# 1-Schematic_Synapse.net
KiCad netlist of a schematic drawn in EasyEDA
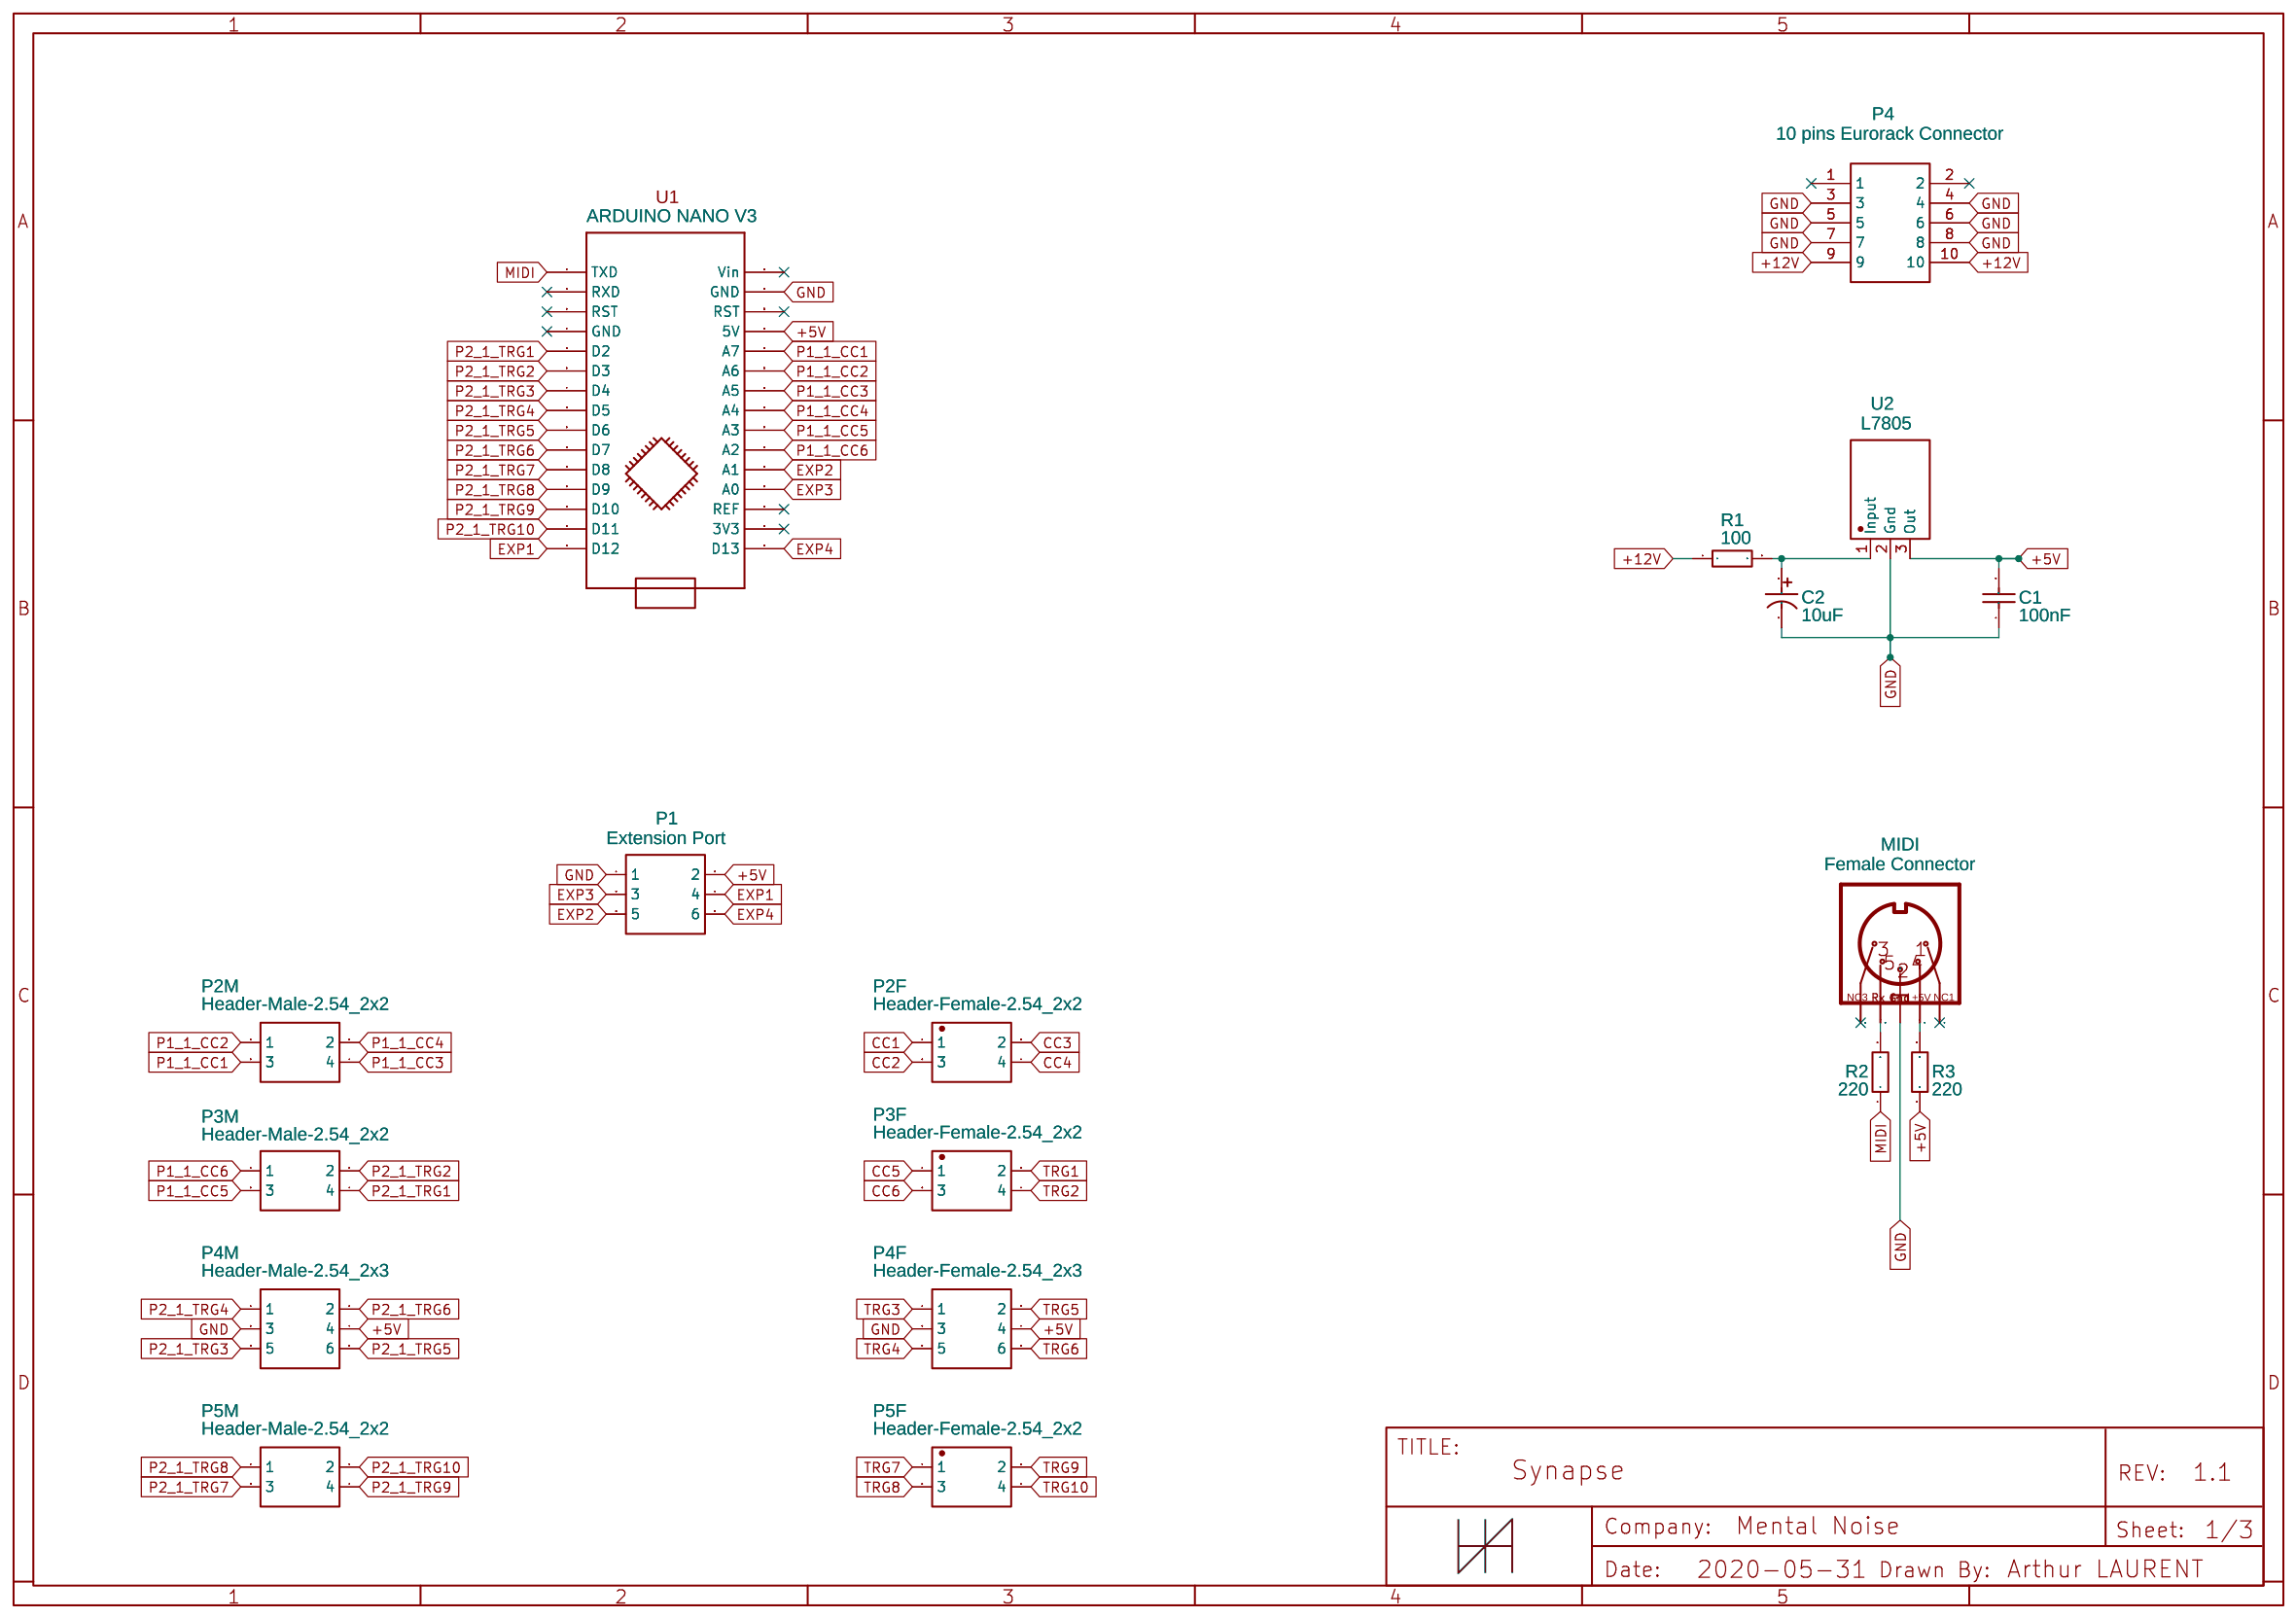
[diagram p0: Arduino]
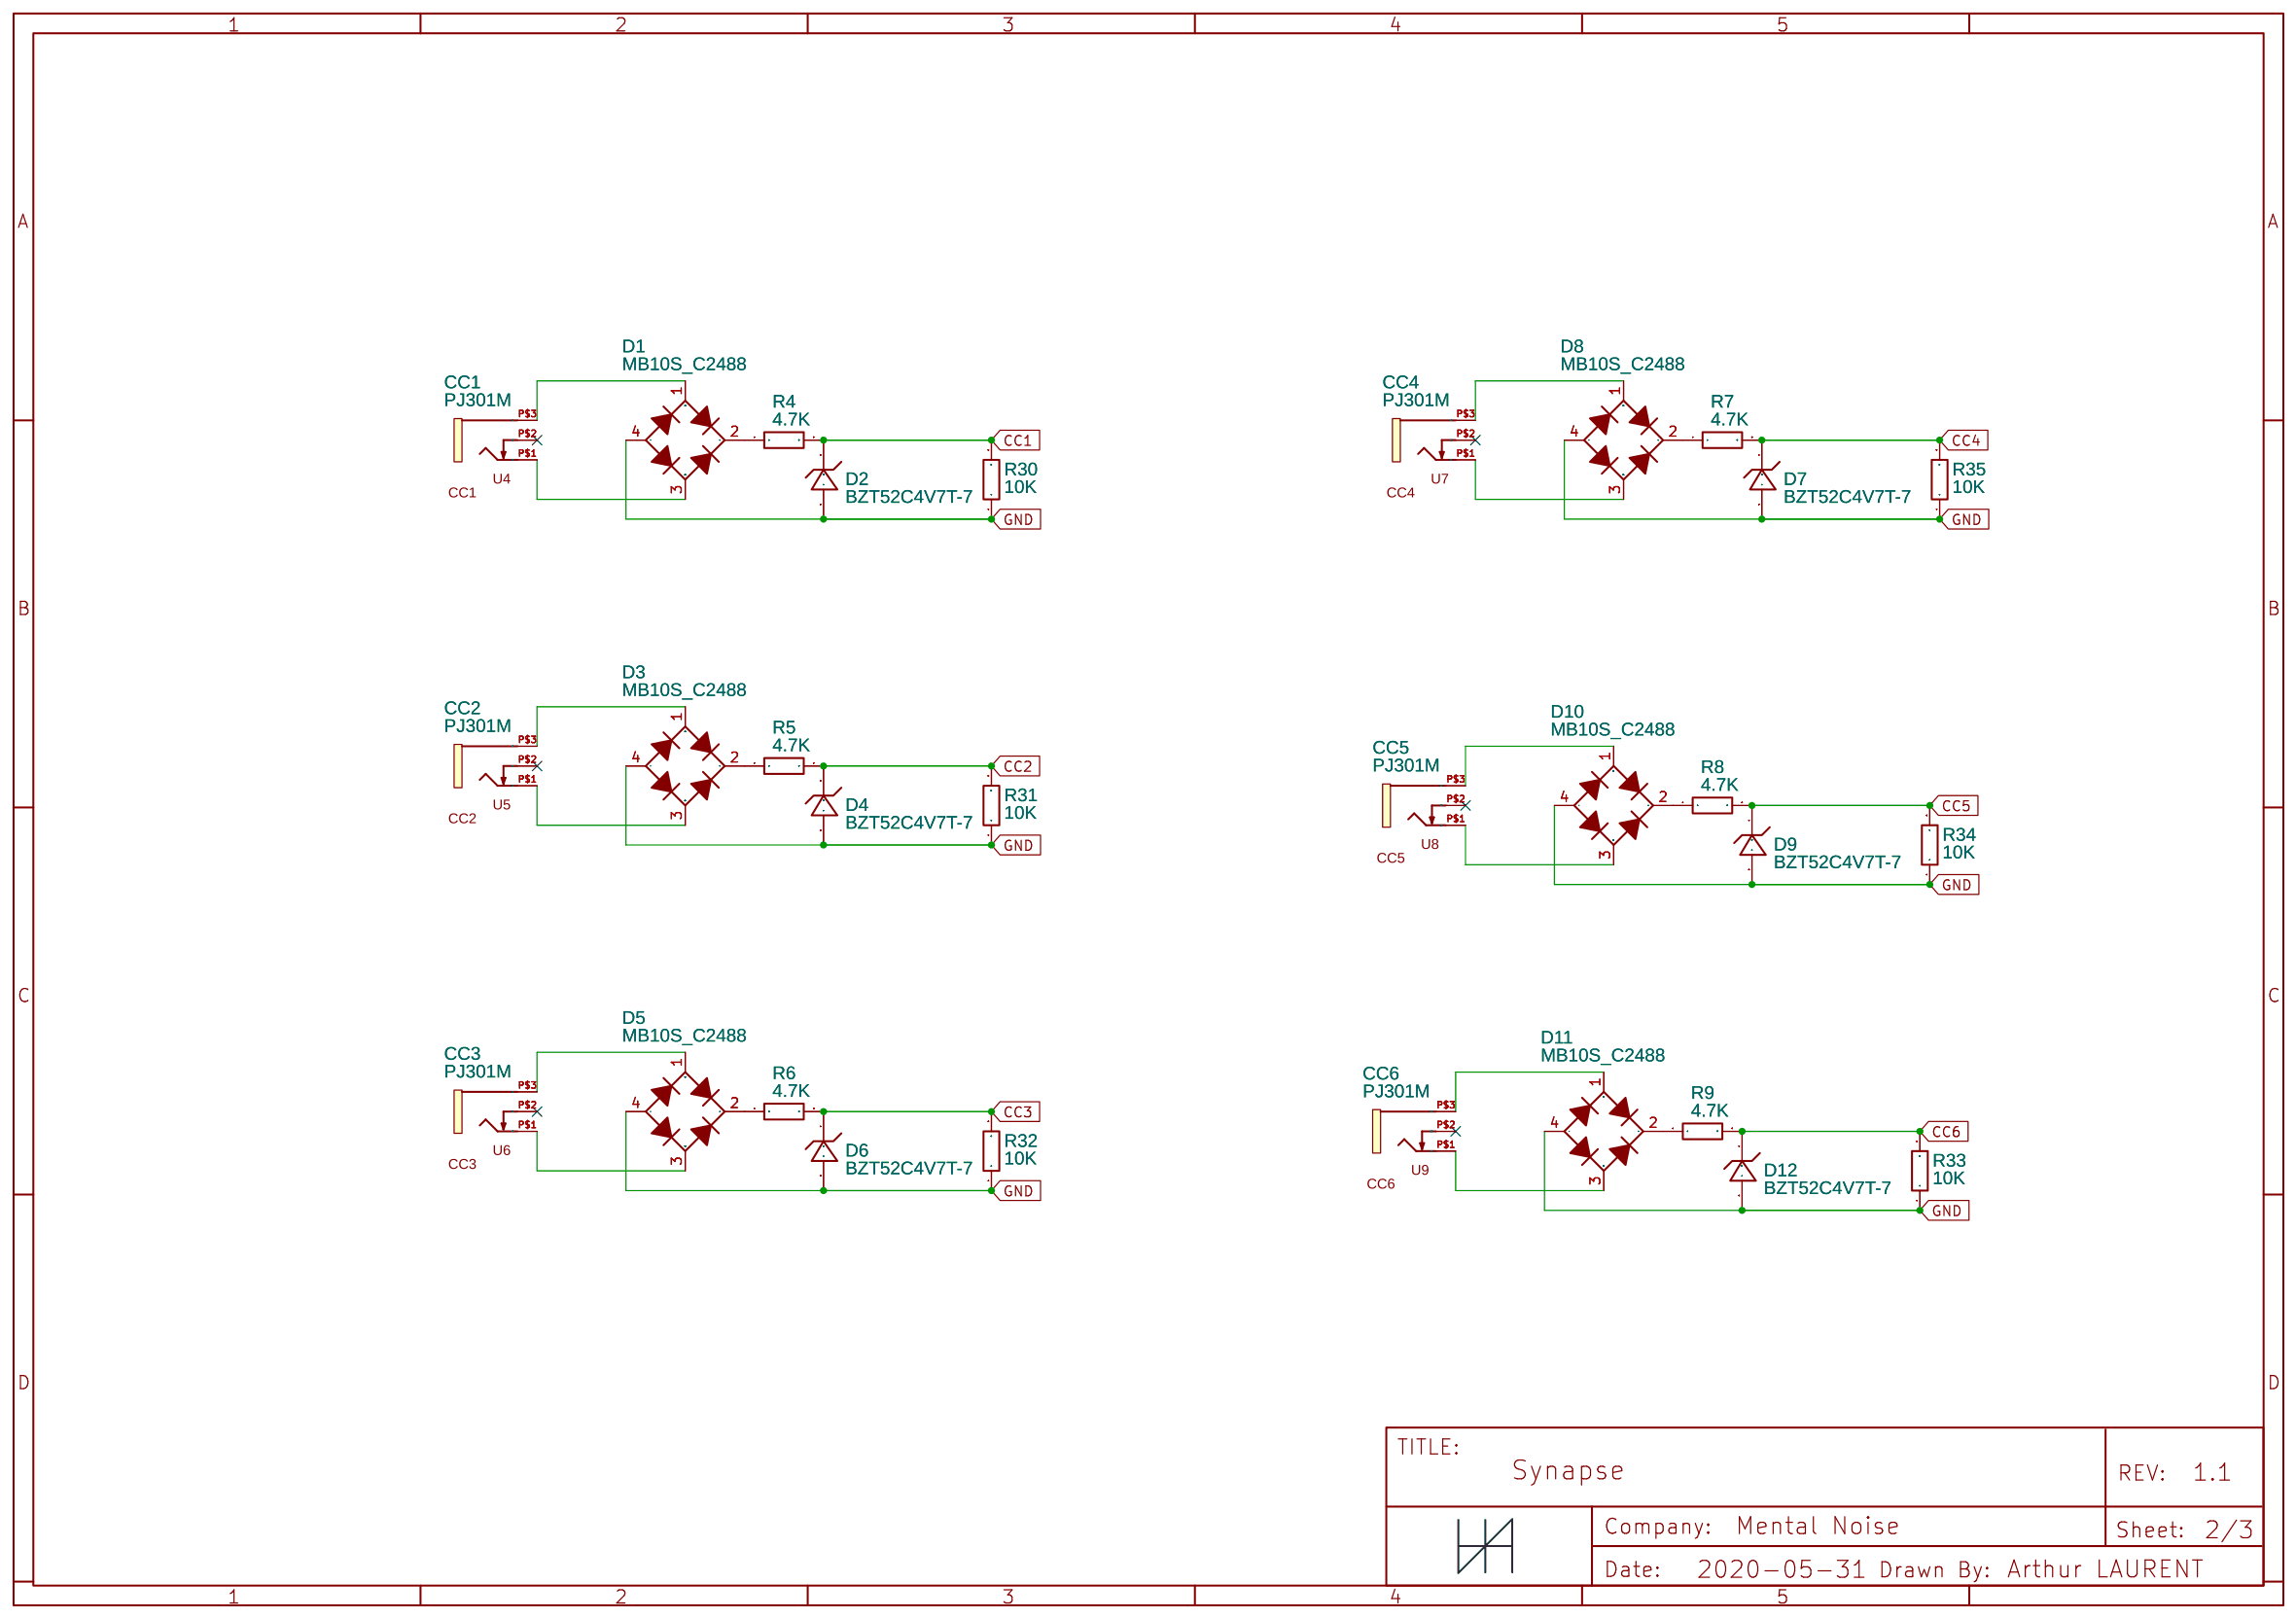
[diagram p1: Control Change]
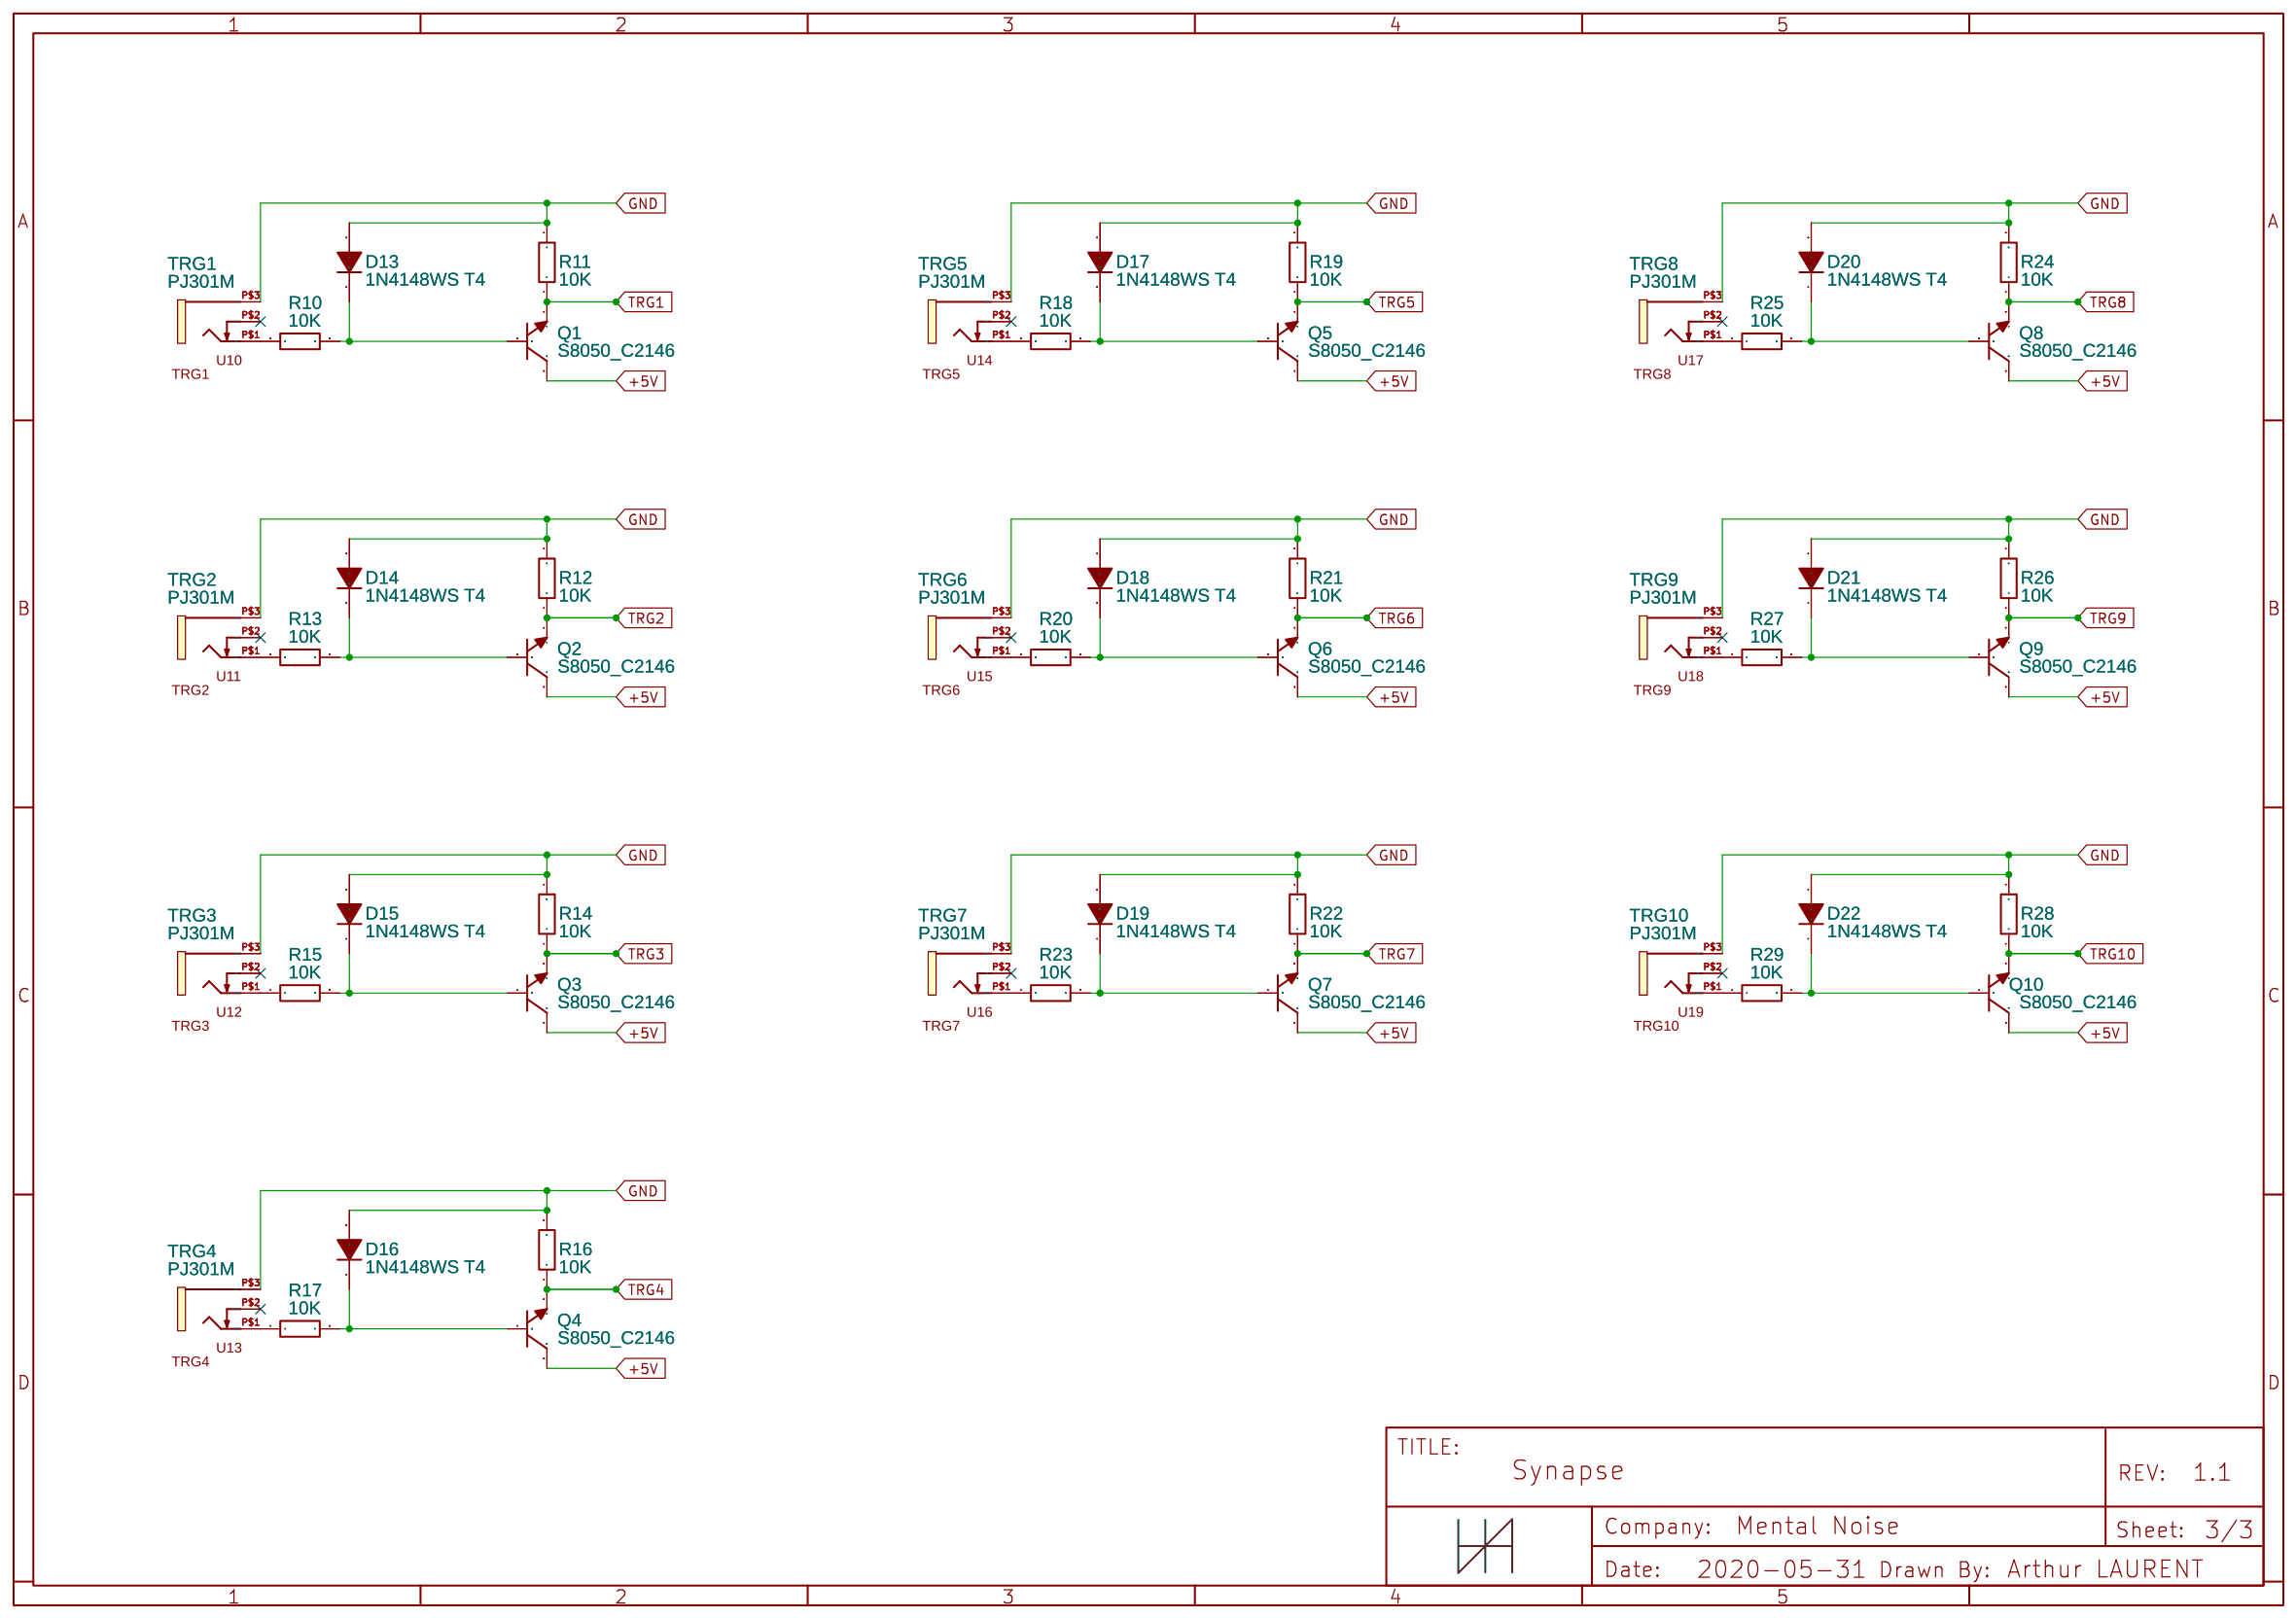
[diagram p2: Trigger]

(export (version "E")
  (design (tool "Eeschema 10.0.6"))
  (components
    (comp (ref "C1")
      (value "100nF")
      (fields (field (name "BOM_Manufacturer Part") "Ceramic capacitor0.1UF50V"))
      (libsource (lib "") (part "CERAMIC CAPACITOR_100nF"))
    )
    (comp (ref "C2")
      (value "10uF")
      (fields
        (field (name "BOM_Manufacturer Part") "10uF 50V 5*11")
        (field (name "BOM_Supplier Part") "C43345")
      )
      (libsource (lib "") (part "10uF 50V 5*11"))
    )
    (comp (ref "MIDI") (value "Female Connector") (libsource (lib "") (part "MIDI Connector")))
    (comp (ref "P1")
      (value "Extension Port")
      (fields
        (field (name "BOM_Manufacturer Part") "2X3 2.54mm IDC Box")
        (field (name "BOM_Supplier Part") "C11214")
      )
      (libsource (lib "") (part "HDR-IDC-2.54-2X3P"))
    )
    (comp (ref "P2F")
      (value "Header-Female-2.54_2x2")
      (fields
        (field (name "BOM_Manufacturer Part") "DS1023-2*2SF11")
        (field (name "BOM_Supplier Part") "C92273")
      )
      (libsource (lib "") (part "Header-Female-2.54_2x2"))
    )
    (comp (ref "P2M")
      (value "Header-Male-2.54_2x2")
      (fields
        (field (name "BOM_Manufacturer Part") "Double Rows2.54mm2*2pHeaders  Pins")
        (field (name "BOM_Supplier Part") "C66690")
      )
      (libsource (lib "") (part "Header-Male-2.54_2x2_2"))
    )
    (comp (ref "P3F")
      (value "Header-Female-2.54_2x2")
      (fields
        (field (name "BOM_Manufacturer Part") "DS1023-2*2SF11")
        (field (name "BOM_Supplier Part") "C92273")
      )
      (libsource (lib "") (part "Header-Female-2.54_2x2_1"))
    )
    (comp (ref "P3M")
      (value "Header-Male-2.54_2x2")
      (fields
        (field (name "BOM_Manufacturer Part") "Double Rows2.54mm2*2pHeaders  Pins")
        (field (name "BOM_Supplier Part") "C66690")
      )
      (libsource (lib "") (part "Header-Male-2.54_2x2_1"))
    )
    (comp (ref "P4")
      (value "10 pins Eurorack Connector")
      (fields
        (field (name "BOM_Manufacturer Part") "TST-105-02-G-D")
        (field (name "BOM_Supplier Part") "C131327")
      )
      (libsource (lib "") (part "CONN ISP 10P"))
    )
    (comp (ref "P4F")
      (value "Header-Female-2.54_2x3")
      (fields
        (field (name "BOM_Manufacturer Part") "DS1023-2*3SF11")
        (field (name "BOM_Supplier Part") "C92272")
      )
      (libsource (lib "") (part "Header-Female-2.54_2x3"))
    )
    (comp (ref "P4M")
      (value "Header-Male-2.54_2x3")
      (fields (field (name "BOM_Supplier Part") "C65114"))
      (libsource (lib "") (part "Header-Male-2.54_2x3"))
    )
    (comp (ref "P5F")
      (value "Header-Female-2.54_2x2")
      (fields
        (field (name "BOM_Manufacturer Part") "DS1023-2*2SF11")
        (field (name "BOM_Supplier Part") "C92273")
      )
      (libsource (lib "") (part "Header-Female-2.54_2x2_2"))
    )
    (comp (ref "P5M")
      (value "Header-Male-2.54_2x2")
      (fields
        (field (name "BOM_Manufacturer Part") "Double Rows2.54mm2*2pHeaders  Pins")
        (field (name "BOM_Supplier Part") "C66690")
      )
      (libsource (lib "") (part "Header-Male-2.54_2x2"))
    )
    (comp (ref "R1")
      (value "100")
      (fields (field (name "BOM_Supplier Part") "C119304"))
      (libsource (lib "") (part "MF1/4W-100Ω±1% T52"))
    )
    (comp (ref "R2")
      (value "220")
      (fields
        (field (name "BOM_Manufacturer Part") "MFR0W4F2200A50")
        (field (name "BOM_Supplier Part") "C57439")
      )
      (libsource (lib "") (part "MFR0W4F2200A50"))
    )
    (comp (ref "R3")
      (value "220")
      (fields
        (field (name "BOM_Manufacturer Part") "MFR0W4F2200A50")
        (field (name "BOM_Supplier Part") "C57439")
      )
      (libsource (lib "") (part "MFR0W4F2200A50"))
    )
    (comp (ref "U1")
      (value "ARDUINO NANO V3")
      (fields (field (name "BOM_Manufacturer Part") "arduino_nano1"))
      (libsource (lib "") (part "ARDUINO NANO V3"))
    )
    (comp (ref "U2")
      (value "L7805")
      (fields (field (name "BOM_Manufacturer Part") "L7805CV") (field (name "BOM_Supplier Part") "C347289"))
      (libsource (lib "") (part "L7805CV_C347289"))
    )
    (comp (ref "CC1") (value "PJ301M") (libsource (lib "") (part "PJ301M_1")))
    (comp (ref "CC2") (value "PJ301M") (libsource (lib "") (part "PJ301M_5")))
    (comp (ref "CC3") (value "PJ301M") (libsource (lib "") (part "PJ301M")))
    (comp (ref "CC4") (value "PJ301M") (libsource (lib "") (part "PJ301M_4")))
    (comp (ref "CC5") (value "PJ301M") (libsource (lib "") (part "PJ301M_2")))
    (comp (ref "CC6") (value "PJ301M") (libsource (lib "") (part "PJ301M_3")))
    (comp (ref "D1")
      (value "MB10S_C2488")
      (fields (field (name "BOM_Manufacturer Part") "MB10S") (field (name "BOM_Supplier Part") "C2488"))
      (libsource (lib "") (part "MB10S_C2488"))
    )
    (comp (ref "D2")
      (value "BZT52C4V7T-7")
      (fields (field (name "BOM_Supplier Part") "C151452"))
      (libsource (lib "") (part "BZT52C4V7T-7"))
    )
    (comp (ref "D3")
      (value "MB10S_C2488")
      (fields (field (name "BOM_Manufacturer Part") "MB10S") (field (name "BOM_Supplier Part") "C2488"))
      (libsource (lib "") (part "MB10S_C2488"))
    )
    (comp (ref "D4")
      (value "BZT52C4V7T-7")
      (fields (field (name "BOM_Supplier Part") "C151452"))
      (libsource (lib "") (part "BZT52C4V7T-7"))
    )
    (comp (ref "D5")
      (value "MB10S_C2488")
      (fields (field (name "BOM_Manufacturer Part") "MB10S") (field (name "BOM_Supplier Part") "C2488"))
      (libsource (lib "") (part "MB10S_C2488"))
    )
    (comp (ref "D6")
      (value "BZT52C4V7T-7")
      (fields (field (name "BOM_Supplier Part") "C151452"))
      (libsource (lib "") (part "BZT52C4V7T-7"))
    )
    (comp (ref "D7")
      (value "BZT52C4V7T-7")
      (fields (field (name "BOM_Supplier Part") "C151452"))
      (libsource (lib "") (part "BZT52C4V7T-7"))
    )
    (comp (ref "D8")
      (value "MB10S_C2488")
      (fields (field (name "BOM_Manufacturer Part") "MB10S") (field (name "BOM_Supplier Part") "C2488"))
      (libsource (lib "") (part "MB10S_C2488"))
    )
    (comp (ref "D9")
      (value "BZT52C4V7T-7")
      (fields (field (name "BOM_Supplier Part") "C151452"))
      (libsource (lib "") (part "BZT52C4V7T-7"))
    )
    (comp (ref "D10")
      (value "MB10S_C2488")
      (fields (field (name "BOM_Manufacturer Part") "MB10S") (field (name "BOM_Supplier Part") "C2488"))
      (libsource (lib "") (part "MB10S_C2488"))
    )
    (comp (ref "D11")
      (value "MB10S_C2488")
      (fields (field (name "BOM_Manufacturer Part") "MB10S") (field (name "BOM_Supplier Part") "C2488"))
      (libsource (lib "") (part "MB10S_C2488"))
    )
    (comp (ref "D12")
      (value "BZT52C4V7T-7")
      (fields (field (name "BOM_Supplier Part") "C151452"))
      (libsource (lib "") (part "BZT52C4V7T-7"))
    )
    (comp (ref "R4")
      (value "4.7K")
      (fields
        (field (name "BOM_Manufacturer Part") "0402WGF4701TCE")
        (field (name "BOM_Supplier Part") "C25900")
      )
      (libsource (lib "") (part "0402WGF4701TCE"))
    )
    (comp (ref "R5")
      (value "4.7K")
      (fields
        (field (name "BOM_Manufacturer Part") "0402WGF4701TCE")
        (field (name "BOM_Supplier Part") "C25900")
      )
      (libsource (lib "") (part "0402WGF4701TCE"))
    )
    (comp (ref "R6")
      (value "4.7K")
      (fields
        (field (name "BOM_Manufacturer Part") "0402WGF4701TCE")
        (field (name "BOM_Supplier Part") "C25900")
      )
      (libsource (lib "") (part "0402WGF4701TCE"))
    )
    (comp (ref "R7")
      (value "4.7K")
      (fields
        (field (name "BOM_Manufacturer Part") "0402WGF4701TCE")
        (field (name "BOM_Supplier Part") "C25900")
      )
      (libsource (lib "") (part "0402WGF4701TCE"))
    )
    (comp (ref "R8")
      (value "4.7K")
      (fields
        (field (name "BOM_Manufacturer Part") "0402WGF4701TCE")
        (field (name "BOM_Supplier Part") "C25900")
      )
      (libsource (lib "") (part "0402WGF4701TCE"))
    )
    (comp (ref "R9")
      (value "4.7K")
      (fields
        (field (name "BOM_Manufacturer Part") "0402WGF4701TCE")
        (field (name "BOM_Supplier Part") "C25900")
      )
      (libsource (lib "") (part "0402WGF4701TCE"))
    )
    (comp (ref "R30")
      (value "10K")
      (fields
        (field (name "BOM_Manufacturer Part") "0402WGF1002TCE")
        (field (name "BOM_Supplier Part") "C25744")
      )
      (libsource (lib "") (part "0402WGF1002TCE"))
    )
    (comp (ref "R31")
      (value "10K")
      (fields
        (field (name "BOM_Manufacturer Part") "0402WGF1002TCE")
        (field (name "BOM_Supplier Part") "C25744")
      )
      (libsource (lib "") (part "0402WGF1002TCE"))
    )
    (comp (ref "R32")
      (value "10K")
      (fields
        (field (name "BOM_Manufacturer Part") "0402WGF1002TCE")
        (field (name "BOM_Supplier Part") "C25744")
      )
      (libsource (lib "") (part "0402WGF1002TCE"))
    )
    (comp (ref "R33")
      (value "10K")
      (fields
        (field (name "BOM_Manufacturer Part") "0402WGF1002TCE")
        (field (name "BOM_Supplier Part") "C25744")
      )
      (libsource (lib "") (part "0402WGF1002TCE"))
    )
    (comp (ref "R34")
      (value "10K")
      (fields
        (field (name "BOM_Manufacturer Part") "0402WGF1002TCE")
        (field (name "BOM_Supplier Part") "C25744")
      )
      (libsource (lib "") (part "0402WGF1002TCE"))
    )
    (comp (ref "R35")
      (value "10K")
      (fields
        (field (name "BOM_Manufacturer Part") "0402WGF1002TCE")
        (field (name "BOM_Supplier Part") "C25744")
      )
      (libsource (lib "") (part "0402WGF1002TCE"))
    )
    (comp (ref "D13")
      (value "1N4148WS T4")
      (fields (field (name "BOM_Supplier Part") "C2128"))
      (libsource (lib "") (part "1N4148WS T4"))
    )
    (comp (ref "D14")
      (value "1N4148WS T4")
      (fields (field (name "BOM_Supplier Part") "C2128"))
      (libsource (lib "") (part "1N4148WS T4"))
    )
    (comp (ref "D15")
      (value "1N4148WS T4")
      (fields (field (name "BOM_Supplier Part") "C2128"))
      (libsource (lib "") (part "1N4148WS T4"))
    )
    (comp (ref "D16")
      (value "1N4148WS T4")
      (fields (field (name "BOM_Supplier Part") "C2128"))
      (libsource (lib "") (part "1N4148WS T4"))
    )
    (comp (ref "D17")
      (value "1N4148WS T4")
      (fields (field (name "BOM_Supplier Part") "C2128"))
      (libsource (lib "") (part "1N4148WS T4"))
    )
    (comp (ref "D18")
      (value "1N4148WS T4")
      (fields (field (name "BOM_Supplier Part") "C2128"))
      (libsource (lib "") (part "1N4148WS T4"))
    )
    (comp (ref "D19")
      (value "1N4148WS T4")
      (fields (field (name "BOM_Supplier Part") "C2128"))
      (libsource (lib "") (part "1N4148WS T4"))
    )
    (comp (ref "D20")
      (value "1N4148WS T4")
      (fields (field (name "BOM_Supplier Part") "C2128"))
      (libsource (lib "") (part "1N4148WS T4"))
    )
    (comp (ref "D21")
      (value "1N4148WS T4")
      (fields (field (name "BOM_Supplier Part") "C2128"))
      (libsource (lib "") (part "1N4148WS T4"))
    )
    (comp (ref "D22")
      (value "1N4148WS T4")
      (fields (field (name "BOM_Supplier Part") "C2128"))
      (libsource (lib "") (part "1N4148WS T4"))
    )
    (comp (ref "Q1")
      (value "S8050_C2146")
      (fields (field (name "BOM_Manufacturer Part") "S8050") (field (name "BOM_Supplier Part") "C2146"))
      (libsource (lib "") (part "S8050_C2146"))
    )
    (comp (ref "Q2")
      (value "S8050_C2146")
      (fields (field (name "BOM_Manufacturer Part") "S8050") (field (name "BOM_Supplier Part") "C2146"))
      (libsource (lib "") (part "S8050_C2146"))
    )
    (comp (ref "Q3")
      (value "S8050_C2146")
      (fields (field (name "BOM_Manufacturer Part") "S8050") (field (name "BOM_Supplier Part") "C2146"))
      (libsource (lib "") (part "S8050_C2146"))
    )
    (comp (ref "Q4")
      (value "S8050_C2146")
      (fields (field (name "BOM_Manufacturer Part") "S8050") (field (name "BOM_Supplier Part") "C2146"))
      (libsource (lib "") (part "S8050_C2146"))
    )
    (comp (ref "Q5")
      (value "S8050_C2146")
      (fields (field (name "BOM_Manufacturer Part") "S8050") (field (name "BOM_Supplier Part") "C2146"))
      (libsource (lib "") (part "S8050_C2146"))
    )
    (comp (ref "Q6")
      (value "S8050_C2146")
      (fields (field (name "BOM_Manufacturer Part") "S8050") (field (name "BOM_Supplier Part") "C2146"))
      (libsource (lib "") (part "S8050_C2146"))
    )
    (comp (ref "Q7")
      (value "S8050_C2146")
      (fields (field (name "BOM_Manufacturer Part") "S8050") (field (name "BOM_Supplier Part") "C2146"))
      (libsource (lib "") (part "S8050_C2146"))
    )
    (comp (ref "Q8")
      (value "S8050_C2146")
      (fields (field (name "BOM_Manufacturer Part") "S8050") (field (name "BOM_Supplier Part") "C2146"))
      (libsource (lib "") (part "S8050_C2146"))
    )
    (comp (ref "Q9")
      (value "S8050_C2146")
      (fields (field (name "BOM_Manufacturer Part") "S8050") (field (name "BOM_Supplier Part") "C2146"))
      (libsource (lib "") (part "S8050_C2146"))
    )
    (comp (ref "Q10")
      (value "S8050_C2146")
      (fields (field (name "BOM_Manufacturer Part") "S8050") (field (name "BOM_Supplier Part") "C2146"))
      (libsource (lib "") (part "S8050_C2146"))
    )
    (comp (ref "R10")
      (value "10K")
      (fields
        (field (name "BOM_Manufacturer Part") "0402WGF1002TCE")
        (field (name "BOM_Supplier Part") "C25744")
      )
      (libsource (lib "") (part "0402WGF1002TCE"))
    )
    (comp (ref "R11")
      (value "10K")
      (fields
        (field (name "BOM_Manufacturer Part") "0402WGF1002TCE")
        (field (name "BOM_Supplier Part") "C25744")
      )
      (libsource (lib "") (part "0402WGF1002TCE_1"))
    )
    (comp (ref "R12")
      (value "10K")
      (fields
        (field (name "BOM_Manufacturer Part") "0402WGF1002TCE")
        (field (name "BOM_Supplier Part") "C25744")
      )
      (libsource (lib "") (part "0402WGF1002TCE_1"))
    )
    (comp (ref "R13")
      (value "10K")
      (fields
        (field (name "BOM_Manufacturer Part") "0402WGF1002TCE")
        (field (name "BOM_Supplier Part") "C25744")
      )
      (libsource (lib "") (part "0402WGF1002TCE"))
    )
    (comp (ref "R14")
      (value "10K")
      (fields
        (field (name "BOM_Manufacturer Part") "0402WGF1002TCE")
        (field (name "BOM_Supplier Part") "C25744")
      )
      (libsource (lib "") (part "0402WGF1002TCE_1"))
    )
    (comp (ref "R15")
      (value "10K")
      (fields
        (field (name "BOM_Manufacturer Part") "0402WGF1002TCE")
        (field (name "BOM_Supplier Part") "C25744")
      )
      (libsource (lib "") (part "0402WGF1002TCE"))
    )
    (comp (ref "R16")
      (value "10K")
      (fields
        (field (name "BOM_Manufacturer Part") "0402WGF1002TCE")
        (field (name "BOM_Supplier Part") "C25744")
      )
      (libsource (lib "") (part "0402WGF1002TCE_1"))
    )
    (comp (ref "R17")
      (value "10K")
      (fields
        (field (name "BOM_Manufacturer Part") "0402WGF1002TCE")
        (field (name "BOM_Supplier Part") "C25744")
      )
      (libsource (lib "") (part "0402WGF1002TCE"))
    )
    (comp (ref "R18")
      (value "10K")
      (fields
        (field (name "BOM_Manufacturer Part") "0402WGF1002TCE")
        (field (name "BOM_Supplier Part") "C25744")
      )
      (libsource (lib "") (part "0402WGF1002TCE"))
    )
    (comp (ref "R19")
      (value "10K")
      (fields
        (field (name "BOM_Manufacturer Part") "0402WGF1002TCE")
        (field (name "BOM_Supplier Part") "C25744")
      )
      (libsource (lib "") (part "0402WGF1002TCE_1"))
    )
    (comp (ref "R20")
      (value "10K")
      (fields
        (field (name "BOM_Manufacturer Part") "0402WGF1002TCE")
        (field (name "BOM_Supplier Part") "C25744")
      )
      (libsource (lib "") (part "0402WGF1002TCE"))
    )
    (comp (ref "R21")
      (value "10K")
      (fields
        (field (name "BOM_Manufacturer Part") "0402WGF1002TCE")
        (field (name "BOM_Supplier Part") "C25744")
      )
      (libsource (lib "") (part "0402WGF1002TCE_1"))
    )
    (comp (ref "R22")
      (value "10K")
      (fields
        (field (name "BOM_Manufacturer Part") "0402WGF1002TCE")
        (field (name "BOM_Supplier Part") "C25744")
      )
      (libsource (lib "") (part "0402WGF1002TCE_1"))
    )
    (comp (ref "R23")
      (value "10K")
      (fields
        (field (name "BOM_Manufacturer Part") "0402WGF1002TCE")
        (field (name "BOM_Supplier Part") "C25744")
      )
      (libsource (lib "") (part "0402WGF1002TCE"))
    )
    (comp (ref "R24")
      (value "10K")
      (fields
        (field (name "BOM_Manufacturer Part") "0402WGF1002TCE")
        (field (name "BOM_Supplier Part") "C25744")
      )
      (libsource (lib "") (part "0402WGF1002TCE_1"))
    )
    (comp (ref "R25")
      (value "10K")
      (fields
        (field (name "BOM_Manufacturer Part") "0402WGF1002TCE")
        (field (name "BOM_Supplier Part") "C25744")
      )
      (libsource (lib "") (part "0402WGF1002TCE"))
    )
    (comp (ref "R26")
      (value "10K")
      (fields
        (field (name "BOM_Manufacturer Part") "0402WGF1002TCE")
        (field (name "BOM_Supplier Part") "C25744")
      )
      (libsource (lib "") (part "0402WGF1002TCE_1"))
    )
    (comp (ref "R27")
      (value "10K")
      (fields
        (field (name "BOM_Manufacturer Part") "0402WGF1002TCE")
        (field (name "BOM_Supplier Part") "C25744")
      )
      (libsource (lib "") (part "0402WGF1002TCE"))
    )
    (comp (ref "R28")
      (value "10K")
      (fields
        (field (name "BOM_Manufacturer Part") "0402WGF1002TCE")
        (field (name "BOM_Supplier Part") "C25744")
      )
      (libsource (lib "") (part "0402WGF1002TCE_1"))
    )
    (comp (ref "R29")
      (value "10K")
      (fields
        (field (name "BOM_Manufacturer Part") "0402WGF1002TCE")
        (field (name "BOM_Supplier Part") "C25744")
      )
      (libsource (lib "") (part "0402WGF1002TCE"))
    )
    (comp (ref "TRG1") (value "PJ301M") (libsource (lib "") (part "PJ301M_6")))
    (comp (ref "TRG2") (value "PJ301M") (libsource (lib "") (part "PJ301M_8")))
    (comp (ref "TRG3") (value "PJ301M") (libsource (lib "") (part "PJ301M_9")))
    (comp (ref "TRG4") (value "PJ301M") (libsource (lib "") (part "PJ301M_5")))
    (comp (ref "TRG5") (value "PJ301M") (libsource (lib "") (part "PJ301M")))
    (comp (ref "TRG6") (value "PJ301M") (libsource (lib "") (part "PJ301M_7")))
    (comp (ref "TRG7") (value "PJ301M") (libsource (lib "") (part "PJ301M_4")))
    (comp (ref "TRG8") (value "PJ301M") (libsource (lib "") (part "PJ301M_2")))
    (comp (ref "TRG9") (value "PJ301M") (libsource (lib "") (part "PJ301M_1")))
    (comp (ref "TRG10") (value "PJ301M") (libsource (lib "") (part "PJ301M_3")))
  )
  (nets
    (net (code "1") (name "+5V") (class "Default")
      (node (ref "C1") (pin "2") (pinfunction "2_2") (pintype "input"))
      (node (ref "P1") (pin "2") (pinfunction "2_2") (pintype "unspecified"))
      (node (ref "P4F") (pin "4") (pinfunction "4_4") (pintype "input"))
      (node (ref "P4M") (pin "4") (pinfunction "4_4") (pintype "input"))
      (node (ref "Q1") (pin "3") (pinfunction "C_3") (pintype "unspecified"))
      (node (ref "Q10") (pin "3") (pinfunction "C_3") (pintype "unspecified"))
      (node (ref "Q2") (pin "3") (pinfunction "C_3") (pintype "unspecified"))
      (node (ref "Q3") (pin "3") (pinfunction "C_3") (pintype "unspecified"))
      (node (ref "Q4") (pin "3") (pinfunction "C_3") (pintype "unspecified"))
      (node (ref "Q5") (pin "3") (pinfunction "C_3") (pintype "unspecified"))
      (node (ref "Q6") (pin "3") (pinfunction "C_3") (pintype "unspecified"))
      (node (ref "Q7") (pin "3") (pinfunction "C_3") (pintype "unspecified"))
      (node (ref "Q8") (pin "3") (pinfunction "C_3") (pintype "unspecified"))
      (node (ref "Q9") (pin "3") (pinfunction "C_3") (pintype "unspecified"))
      (node (ref "R3") (pin "1") (pinfunction "1_1") (pintype "input"))
      (node (ref "U1") (pin "27") (pinfunction "5V_27") (pintype "output"))
      (node (ref "U2") (pin "3") (pinfunction "Out_3") (pintype "unspecified"))
    )
    (net (code "2") (name "+12V") (class "Default")
      (node (ref "P4") (pin "10") (pinfunction "10_10") (pintype "unspecified"))
      (node (ref "P4") (pin "9") (pinfunction "9_9") (pintype "unspecified"))
      (node (ref "R1") (pin "1") (pinfunction "1_1") (pintype "unspecified"))
    )
    (net (code "3") (name "CC1") (class "Default")
      (node (ref "D2") (pin "1") (pinfunction "C_1") (pintype "unspecified"))
      (node (ref "P2F") (pin "1") (pinfunction "1_1") (pintype "unspecified"))
      (node (ref "R30") (pin "2") (pinfunction "2_2") (pintype "input"))
      (node (ref "R4") (pin "2") (pinfunction "2_2") (pintype "input"))
    )
    (net (code "4") (name "CC2") (class "Default")
      (node (ref "D4") (pin "1") (pinfunction "C_1") (pintype "unspecified"))
      (node (ref "P2F") (pin "3") (pinfunction "3_3") (pintype "unspecified"))
      (node (ref "R31") (pin "2") (pinfunction "2_2") (pintype "input"))
      (node (ref "R5") (pin "2") (pinfunction "2_2") (pintype "input"))
    )
    (net (code "5") (name "CC3") (class "Default")
      (node (ref "D6") (pin "1") (pinfunction "C_1") (pintype "unspecified"))
      (node (ref "P2F") (pin "2") (pinfunction "2_2") (pintype "unspecified"))
      (node (ref "R32") (pin "2") (pinfunction "2_2") (pintype "input"))
      (node (ref "R6") (pin "2") (pinfunction "2_2") (pintype "input"))
    )
    (net (code "6") (name "CC4") (class "Default")
      (node (ref "D7") (pin "1") (pinfunction "C_1") (pintype "unspecified"))
      (node (ref "P2F") (pin "4") (pinfunction "4_4") (pintype "unspecified"))
      (node (ref "R35") (pin "2") (pinfunction "2_2") (pintype "input"))
      (node (ref "R7") (pin "2") (pinfunction "2_2") (pintype "input"))
    )
    (net (code "7") (name "CC5") (class "Default")
      (node (ref "D9") (pin "1") (pinfunction "C_1") (pintype "unspecified"))
      (node (ref "P3F") (pin "1") (pinfunction "1_1") (pintype "unspecified"))
      (node (ref "R34") (pin "2") (pinfunction "2_2") (pintype "input"))
      (node (ref "R8") (pin "2") (pinfunction "2_2") (pintype "input"))
    )
    (net (code "8") (name "CC6") (class "Default")
      (node (ref "D12") (pin "1") (pinfunction "C_1") (pintype "unspecified"))
      (node (ref "P3F") (pin "3") (pinfunction "3_3") (pintype "unspecified"))
      (node (ref "R33") (pin "2") (pinfunction "2_2") (pintype "input"))
      (node (ref "R9") (pin "2") (pinfunction "2_2") (pintype "input"))
    )
    (net (code "9") (name "EXP1") (class "Default")
      (node (ref "P1") (pin "4") (pinfunction "4_4") (pintype "unspecified"))
      (node (ref "U1") (pin "15") (pinfunction "D12_15") (pintype "unspecified"))
    )
    (net (code "10") (name "EXP2") (class "Default")
      (node (ref "P1") (pin "5") (pinfunction "5_5") (pintype "unspecified"))
      (node (ref "U1") (pin "20") (pinfunction "A1_20") (pintype "unspecified"))
    )
    (net (code "11") (name "EXP3") (class "Default")
      (node (ref "P1") (pin "3") (pinfunction "3_3") (pintype "unspecified"))
      (node (ref "U1") (pin "19") (pinfunction "A0_19") (pintype "unspecified"))
    )
    (net (code "12") (name "EXP4") (class "Default")
      (node (ref "P1") (pin "6") (pinfunction "6_6") (pintype "unspecified"))
      (node (ref "U1") (pin "16") (pinfunction "D13_16") (pintype "unspecified"))
    )
    (net (code "13") (name "GND") (class "Default")
      (node (ref "C1") (pin "1") (pinfunction "1_1") (pintype "input"))
      (node (ref "C2") (pin "2") (pinfunction "2_2") (pintype "input"))
      (node (ref "D1") (pin "4") (pinfunction "-_4") (pintype "unspecified"))
      (node (ref "D10") (pin "4") (pinfunction "-_4") (pintype "unspecified"))
      (node (ref "D11") (pin "4") (pinfunction "-_4") (pintype "unspecified"))
      (node (ref "D12") (pin "2") (pinfunction "A_2") (pintype "unspecified"))
      (node (ref "D13") (pin "2") (pinfunction "A_2") (pintype "unspecified"))
      (node (ref "D14") (pin "2") (pinfunction "A_2") (pintype "unspecified"))
      (node (ref "D15") (pin "2") (pinfunction "A_2") (pintype "unspecified"))
      (node (ref "D16") (pin "2") (pinfunction "A_2") (pintype "unspecified"))
      (node (ref "D17") (pin "2") (pinfunction "A_2") (pintype "unspecified"))
      (node (ref "D18") (pin "2") (pinfunction "A_2") (pintype "unspecified"))
      (node (ref "D19") (pin "2") (pinfunction "A_2") (pintype "unspecified"))
      (node (ref "D2") (pin "2") (pinfunction "A_2") (pintype "unspecified"))
      (node (ref "D20") (pin "2") (pinfunction "A_2") (pintype "unspecified"))
      (node (ref "D21") (pin "2") (pinfunction "A_2") (pintype "unspecified"))
      (node (ref "D22") (pin "2") (pinfunction "A_2") (pintype "unspecified"))
      (node (ref "D3") (pin "4") (pinfunction "-_4") (pintype "unspecified"))
      (node (ref "D4") (pin "2") (pinfunction "A_2") (pintype "unspecified"))
      (node (ref "D5") (pin "4") (pinfunction "-_4") (pintype "unspecified"))
      (node (ref "D6") (pin "2") (pinfunction "A_2") (pintype "unspecified"))
      (node (ref "D7") (pin "2") (pinfunction "A_2") (pintype "unspecified"))
      (node (ref "D8") (pin "4") (pinfunction "-_4") (pintype "unspecified"))
      (node (ref "D9") (pin "2") (pinfunction "A_2") (pintype "unspecified"))
      (node (ref "MIDI") (pin "2") (pinfunction "2_2") (pintype "unspecified"))
      (node (ref "P1") (pin "1") (pinfunction "1_1") (pintype "unspecified"))
      (node (ref "P4") (pin "3") (pinfunction "3_3") (pintype "unspecified"))
      (node (ref "P4") (pin "4") (pinfunction "4_4") (pintype "unspecified"))
      (node (ref "P4") (pin "5") (pinfunction "5_5") (pintype "unspecified"))
      (node (ref "P4") (pin "6") (pinfunction "6_6") (pintype "unspecified"))
      (node (ref "P4") (pin "7") (pinfunction "7_7") (pintype "unspecified"))
      (node (ref "P4") (pin "8") (pinfunction "8_8") (pintype "unspecified"))
      (node (ref "P4F") (pin "3") (pinfunction "3_3") (pintype "input"))
      (node (ref "P4M") (pin "3") (pinfunction "3_3") (pintype "input"))
      (node (ref "R11") (pin "2") (pinfunction "2_2") (pintype "input"))
      (node (ref "R12") (pin "2") (pinfunction "2_2") (pintype "input"))
      (node (ref "R14") (pin "2") (pinfunction "2_2") (pintype "input"))
      (node (ref "R16") (pin "2") (pinfunction "2_2") (pintype "input"))
      (node (ref "R19") (pin "2") (pinfunction "2_2") (pintype "input"))
      (node (ref "R21") (pin "2") (pinfunction "2_2") (pintype "input"))
      (node (ref "R22") (pin "2") (pinfunction "2_2") (pintype "input"))
      (node (ref "R24") (pin "2") (pinfunction "2_2") (pintype "input"))
      (node (ref "R26") (pin "2") (pinfunction "2_2") (pintype "input"))
      (node (ref "R28") (pin "2") (pinfunction "2_2") (pintype "input"))
      (node (ref "R30") (pin "1") (pinfunction "1_1") (pintype "input"))
      (node (ref "R31") (pin "1") (pinfunction "1_1") (pintype "input"))
      (node (ref "R32") (pin "1") (pinfunction "1_1") (pintype "input"))
      (node (ref "R33") (pin "1") (pinfunction "1_1") (pintype "input"))
      (node (ref "R34") (pin "1") (pinfunction "1_1") (pintype "input"))
      (node (ref "R35") (pin "1") (pinfunction "1_1") (pintype "input"))
      (node (ref "TRG1") (pin "P$3") (pinfunction "1_P$3") (pintype "bidirectional"))
      (node (ref "TRG10") (pin "P$3") (pinfunction "1_P$3") (pintype "bidirectional"))
      (node (ref "TRG2") (pin "P$3") (pinfunction "1_P$3") (pintype "bidirectional"))
      (node (ref "TRG3") (pin "P$3") (pinfunction "1_P$3") (pintype "bidirectional"))
      (node (ref "TRG4") (pin "P$3") (pinfunction "1_P$3") (pintype "bidirectional"))
      (node (ref "TRG5") (pin "P$3") (pinfunction "1_P$3") (pintype "bidirectional"))
      (node (ref "TRG6") (pin "P$3") (pinfunction "1_P$3") (pintype "bidirectional"))
      (node (ref "TRG7") (pin "P$3") (pinfunction "1_P$3") (pintype "bidirectional"))
      (node (ref "TRG8") (pin "P$3") (pinfunction "1_P$3") (pintype "bidirectional"))
      (node (ref "TRG9") (pin "P$3") (pinfunction "1_P$3") (pintype "bidirectional"))
      (node (ref "U1") (pin "29") (pinfunction "GND_29") (pintype "unspecified"))
      (node (ref "U2") (pin "2") (pinfunction "Gnd_2") (pintype "unspecified"))
    )
    (net (code "14") (name "MIDI") (class "Default")
      (node (ref "R2") (pin "1") (pinfunction "1_1") (pintype "input"))
      (node (ref "U1") (pin "1") (pinfunction "TXD_1") (pintype "unspecified"))
    )
    (net (code "15") (name "Net-(CC1-1)") (class "Default")
      (node (ref "CC1") (pin "P$3") (pinfunction "1_P$3") (pintype "bidirectional"))
      (node (ref "D1") (pin "1") (pinfunction "C1_1") (pintype "unspecified"))
    )
    (net (code "16") (name "Net-(CC1-2)") (class "Default")
      (node (ref "CC1") (pin "P$1") (pinfunction "2_P$1") (pintype "bidirectional"))
      (node (ref "D1") (pin "3") (pinfunction "C2_3") (pintype "unspecified"))
    )
    (net (code "17") (name "Net-(CC2-1)") (class "Default")
      (node (ref "CC2") (pin "P$3") (pinfunction "1_P$3") (pintype "bidirectional"))
      (node (ref "D3") (pin "1") (pinfunction "C1_1") (pintype "unspecified"))
    )
    (net (code "18") (name "Net-(CC2-2)") (class "Default")
      (node (ref "CC2") (pin "P$1") (pinfunction "2_P$1") (pintype "bidirectional"))
      (node (ref "D3") (pin "3") (pinfunction "C2_3") (pintype "unspecified"))
    )
    (net (code "19") (name "Net-(CC3-1)") (class "Default")
      (node (ref "CC3") (pin "P$3") (pinfunction "1_P$3") (pintype "bidirectional"))
      (node (ref "D5") (pin "1") (pinfunction "C1_1") (pintype "unspecified"))
    )
    (net (code "20") (name "Net-(CC3-2)") (class "Default")
      (node (ref "CC3") (pin "P$1") (pinfunction "2_P$1") (pintype "bidirectional"))
      (node (ref "D5") (pin "3") (pinfunction "C2_3") (pintype "unspecified"))
    )
    (net (code "21") (name "Net-(CC4-1)") (class "Default")
      (node (ref "CC4") (pin "P$3") (pinfunction "1_P$3") (pintype "bidirectional"))
      (node (ref "D8") (pin "1") (pinfunction "C1_1") (pintype "unspecified"))
    )
    (net (code "22") (name "Net-(CC4-2)") (class "Default")
      (node (ref "CC4") (pin "P$1") (pinfunction "2_P$1") (pintype "bidirectional"))
      (node (ref "D8") (pin "3") (pinfunction "C2_3") (pintype "unspecified"))
    )
    (net (code "23") (name "Net-(CC5-1)") (class "Default")
      (node (ref "CC5") (pin "P$3") (pinfunction "1_P$3") (pintype "bidirectional"))
      (node (ref "D10") (pin "1") (pinfunction "C1_1") (pintype "unspecified"))
    )
    (net (code "24") (name "Net-(CC5-2)") (class "Default")
      (node (ref "CC5") (pin "P$1") (pinfunction "2_P$1") (pintype "bidirectional"))
      (node (ref "D10") (pin "3") (pinfunction "C2_3") (pintype "unspecified"))
    )
    (net (code "25") (name "Net-(CC6-1)") (class "Default")
      (node (ref "CC6") (pin "P$3") (pinfunction "1_P$3") (pintype "bidirectional"))
      (node (ref "D11") (pin "1") (pinfunction "C1_1") (pintype "unspecified"))
    )
    (net (code "26") (name "Net-(CC6-2)") (class "Default")
      (node (ref "CC6") (pin "P$1") (pinfunction "2_P$1") (pintype "bidirectional"))
      (node (ref "D11") (pin "3") (pinfunction "C2_3") (pintype "unspecified"))
    )
    (net (code "27") (name "Net-(D1-+)") (class "Default")
      (node (ref "D1") (pin "2") (pinfunction "+_2") (pintype "unspecified"))
      (node (ref "R4") (pin "1") (pinfunction "1_1") (pintype "input"))
    )
    (net (code "28") (name "Net-(D3-+)") (class "Default")
      (node (ref "D3") (pin "2") (pinfunction "+_2") (pintype "unspecified"))
      (node (ref "R5") (pin "1") (pinfunction "1_1") (pintype "input"))
    )
    (net (code "29") (name "Net-(D5-+)") (class "Default")
      (node (ref "D5") (pin "2") (pinfunction "+_2") (pintype "unspecified"))
      (node (ref "R6") (pin "1") (pinfunction "1_1") (pintype "input"))
    )
    (net (code "30") (name "Net-(D8-+)") (class "Default")
      (node (ref "D8") (pin "2") (pinfunction "+_2") (pintype "unspecified"))
      (node (ref "R7") (pin "1") (pinfunction "1_1") (pintype "input"))
    )
    (net (code "31") (name "Net-(D10-+)") (class "Default")
      (node (ref "D10") (pin "2") (pinfunction "+_2") (pintype "unspecified"))
      (node (ref "R8") (pin "1") (pinfunction "1_1") (pintype "input"))
    )
    (net (code "32") (name "Net-(D11-+)") (class "Default")
      (node (ref "D11") (pin "2") (pinfunction "+_2") (pintype "unspecified"))
      (node (ref "R9") (pin "1") (pinfunction "1_1") (pintype "input"))
    )
    (net (code "33") (name "Net-(D13-K)") (class "Default")
      (node (ref "D13") (pin "1") (pinfunction "K_1") (pintype "unspecified"))
      (node (ref "Q1") (pin "1") (pinfunction "B_1") (pintype "unspecified"))
      (node (ref "R10") (pin "2") (pinfunction "2_2") (pintype "input"))
    )
    (net (code "34") (name "Net-(D14-K)") (class "Default")
      (node (ref "D14") (pin "1") (pinfunction "K_1") (pintype "unspecified"))
      (node (ref "Q2") (pin "1") (pinfunction "B_1") (pintype "unspecified"))
      (node (ref "R13") (pin "2") (pinfunction "2_2") (pintype "input"))
    )
    (net (code "35") (name "Net-(D15-K)") (class "Default")
      (node (ref "D15") (pin "1") (pinfunction "K_1") (pintype "unspecified"))
      (node (ref "Q3") (pin "1") (pinfunction "B_1") (pintype "unspecified"))
      (node (ref "R15") (pin "2") (pinfunction "2_2") (pintype "input"))
    )
    (net (code "36") (name "Net-(D16-K)") (class "Default")
      (node (ref "D16") (pin "1") (pinfunction "K_1") (pintype "unspecified"))
      (node (ref "Q4") (pin "1") (pinfunction "B_1") (pintype "unspecified"))
      (node (ref "R17") (pin "2") (pinfunction "2_2") (pintype "input"))
    )
    (net (code "37") (name "Net-(D17-K)") (class "Default")
      (node (ref "D17") (pin "1") (pinfunction "K_1") (pintype "unspecified"))
      (node (ref "Q5") (pin "1") (pinfunction "B_1") (pintype "unspecified"))
      (node (ref "R18") (pin "2") (pinfunction "2_2") (pintype "input"))
    )
    (net (code "38") (name "Net-(D18-K)") (class "Default")
      (node (ref "D18") (pin "1") (pinfunction "K_1") (pintype "unspecified"))
      (node (ref "Q6") (pin "1") (pinfunction "B_1") (pintype "unspecified"))
      (node (ref "R20") (pin "2") (pinfunction "2_2") (pintype "input"))
    )
    (net (code "39") (name "Net-(D19-K)") (class "Default")
      (node (ref "D19") (pin "1") (pinfunction "K_1") (pintype "unspecified"))
      (node (ref "Q7") (pin "1") (pinfunction "B_1") (pintype "unspecified"))
      (node (ref "R23") (pin "2") (pinfunction "2_2") (pintype "input"))
    )
    (net (code "40") (name "Net-(D20-K)") (class "Default")
      (node (ref "D20") (pin "1") (pinfunction "K_1") (pintype "unspecified"))
      (node (ref "Q8") (pin "1") (pinfunction "B_1") (pintype "unspecified"))
      (node (ref "R25") (pin "2") (pinfunction "2_2") (pintype "input"))
    )
    (net (code "41") (name "Net-(D21-K)") (class "Default")
      (node (ref "D21") (pin "1") (pinfunction "K_1") (pintype "unspecified"))
      (node (ref "Q9") (pin "1") (pinfunction "B_1") (pintype "unspecified"))
      (node (ref "R27") (pin "2") (pinfunction "2_2") (pintype "input"))
    )
    (net (code "42") (name "Net-(D22-K)") (class "Default")
      (node (ref "D22") (pin "1") (pinfunction "K_1") (pintype "unspecified"))
      (node (ref "Q10") (pin "1") (pinfunction "B_1") (pintype "unspecified"))
      (node (ref "R29") (pin "2") (pinfunction "2_2") (pintype "input"))
    )
    (net (code "43") (name "Net-(MIDI-4)") (class "Default")
      (node (ref "MIDI") (pin "3") (pinfunction "4_3") (pintype "unspecified"))
      (node (ref "R3") (pin "2") (pinfunction "2_2") (pintype "input"))
    )
    (net (code "44") (name "Net-(MIDI-5)") (class "Default")
      (node (ref "MIDI") (pin "1") (pinfunction "5_1") (pintype "unspecified"))
      (node (ref "R2") (pin "2") (pinfunction "2_2") (pintype "input"))
    )
    (net (code "45") (name "Net-(TRG1-2)") (class "Default")
      (node (ref "R10") (pin "1") (pinfunction "1_1") (pintype "input"))
      (node (ref "TRG1") (pin "P$1") (pinfunction "2_P$1") (pintype "bidirectional"))
    )
    (net (code "46") (name "Net-(TRG2-2)") (class "Default")
      (node (ref "R13") (pin "1") (pinfunction "1_1") (pintype "input"))
      (node (ref "TRG2") (pin "P$1") (pinfunction "2_P$1") (pintype "bidirectional"))
    )
    (net (code "47") (name "Net-(TRG3-2)") (class "Default")
      (node (ref "R15") (pin "1") (pinfunction "1_1") (pintype "input"))
      (node (ref "TRG3") (pin "P$1") (pinfunction "2_P$1") (pintype "bidirectional"))
    )
    (net (code "48") (name "Net-(TRG4-2)") (class "Default")
      (node (ref "R17") (pin "1") (pinfunction "1_1") (pintype "input"))
      (node (ref "TRG4") (pin "P$1") (pinfunction "2_P$1") (pintype "bidirectional"))
    )
    (net (code "49") (name "Net-(TRG5-2)") (class "Default")
      (node (ref "R18") (pin "1") (pinfunction "1_1") (pintype "input"))
      (node (ref "TRG5") (pin "P$1") (pinfunction "2_P$1") (pintype "bidirectional"))
    )
    (net (code "50") (name "Net-(TRG6-2)") (class "Default")
      (node (ref "R20") (pin "1") (pinfunction "1_1") (pintype "input"))
      (node (ref "TRG6") (pin "P$1") (pinfunction "2_P$1") (pintype "bidirectional"))
    )
    (net (code "51") (name "Net-(TRG7-2)") (class "Default")
      (node (ref "R23") (pin "1") (pinfunction "1_1") (pintype "input"))
      (node (ref "TRG7") (pin "P$1") (pinfunction "2_P$1") (pintype "bidirectional"))
    )
    (net (code "52") (name "Net-(TRG8-2)") (class "Default")
      (node (ref "R25") (pin "1") (pinfunction "1_1") (pintype "input"))
      (node (ref "TRG8") (pin "P$1") (pinfunction "2_P$1") (pintype "bidirectional"))
    )
    (net (code "53") (name "Net-(TRG9-2)") (class "Default")
      (node (ref "R27") (pin "1") (pinfunction "1_1") (pintype "input"))
      (node (ref "TRG9") (pin "P$1") (pinfunction "2_P$1") (pintype "bidirectional"))
    )
    (net (code "54") (name "Net-(TRG10-2)") (class "Default")
      (node (ref "R29") (pin "1") (pinfunction "1_1") (pintype "input"))
      (node (ref "TRG10") (pin "P$1") (pinfunction "2_P$1") (pintype "bidirectional"))
    )
    (net (code "55") (name "Net-(U2-Input)") (class "Default")
      (node (ref "C2") (pin "1") (pinfunction "1_1") (pintype "input"))
      (node (ref "R1") (pin "2") (pinfunction "2_2") (pintype "unspecified"))
      (node (ref "U2") (pin "1") (pinfunction "Input_1") (pintype "unspecified"))
    )
    (net (code "56") (name "P1_1_CC1") (class "Default")
      (node (ref "P2M") (pin "3") (pinfunction "3_3") (pintype "input"))
      (node (ref "U1") (pin "26") (pinfunction "A7_26") (pintype "unspecified"))
    )
    (net (code "57") (name "P1_1_CC2") (class "Default")
      (node (ref "P2M") (pin "1") (pinfunction "1_1") (pintype "input"))
      (node (ref "U1") (pin "25") (pinfunction "A6_25") (pintype "unspecified"))
    )
    (net (code "58") (name "P1_1_CC3") (class "Default")
      (node (ref "P2M") (pin "4") (pinfunction "4_4") (pintype "input"))
      (node (ref "U1") (pin "24") (pinfunction "A5_24") (pintype "unspecified"))
    )
    (net (code "59") (name "P1_1_CC4") (class "Default")
      (node (ref "P2M") (pin "2") (pinfunction "2_2") (pintype "input"))
      (node (ref "U1") (pin "23") (pinfunction "A4_23") (pintype "unspecified"))
    )
    (net (code "60") (name "P1_1_CC5") (class "Default")
      (node (ref "P3M") (pin "3") (pinfunction "3_3") (pintype "input"))
      (node (ref "U1") (pin "22") (pinfunction "A3_22") (pintype "unspecified"))
    )
    (net (code "61") (name "P1_1_CC6") (class "Default")
      (node (ref "P3M") (pin "1") (pinfunction "1_1") (pintype "input"))
      (node (ref "U1") (pin "21") (pinfunction "A2_21") (pintype "unspecified"))
    )
    (net (code "62") (name "P2_1_TRG1") (class "Default")
      (node (ref "P3M") (pin "4") (pinfunction "4_4") (pintype "input"))
      (node (ref "U1") (pin "5") (pinfunction "D2_5") (pintype "unspecified"))
    )
    (net (code "63") (name "P2_1_TRG2") (class "Default")
      (node (ref "P3M") (pin "2") (pinfunction "2_2") (pintype "input"))
      (node (ref "U1") (pin "6") (pinfunction "D3_6") (pintype "unspecified"))
    )
    (net (code "64") (name "P2_1_TRG3") (class "Default")
      (node (ref "P4M") (pin "5") (pinfunction "5_5") (pintype "input"))
      (node (ref "U1") (pin "7") (pinfunction "D4_7") (pintype "unspecified"))
    )
    (net (code "65") (name "P2_1_TRG4") (class "Default")
      (node (ref "P4M") (pin "1") (pinfunction "1_1") (pintype "input"))
      (node (ref "U1") (pin "8") (pinfunction "D5_8") (pintype "unspecified"))
    )
    (net (code "66") (name "P2_1_TRG5") (class "Default")
      (node (ref "P4M") (pin "6") (pinfunction "6_6") (pintype "input"))
      (node (ref "U1") (pin "9") (pinfunction "D6_9") (pintype "unspecified"))
    )
    (net (code "67") (name "P2_1_TRG6") (class "Default")
      (node (ref "P4M") (pin "2") (pinfunction "2_2") (pintype "input"))
      (node (ref "U1") (pin "10") (pinfunction "D7_10") (pintype "unspecified"))
    )
    (net (code "68") (name "P2_1_TRG7") (class "Default")
      (node (ref "P5M") (pin "3") (pinfunction "3_3") (pintype "input"))
      (node (ref "U1") (pin "11") (pinfunction "D8_11") (pintype "unspecified"))
    )
    (net (code "69") (name "P2_1_TRG8") (class "Default")
      (node (ref "P5M") (pin "1") (pinfunction "1_1") (pintype "input"))
      (node (ref "U1") (pin "12") (pinfunction "D9_12") (pintype "unspecified"))
    )
    (net (code "70") (name "P2_1_TRG9") (class "Default")
      (node (ref "P5M") (pin "4") (pinfunction "4_4") (pintype "input"))
      (node (ref "U1") (pin "13") (pinfunction "D10_13") (pintype "unspecified"))
    )
    (net (code "71") (name "P2_1_TRG10") (class "Default")
      (node (ref "P5M") (pin "2") (pinfunction "2_2") (pintype "input"))
      (node (ref "U1") (pin "14") (pinfunction "D11_14") (pintype "unspecified"))
    )
    (net (code "72") (name "TRG1") (class "Default")
      (node (ref "P3F") (pin "2") (pinfunction "2_2") (pintype "unspecified"))
      (node (ref "Q1") (pin "2") (pinfunction "E_2") (pintype "unspecified"))
      (node (ref "R11") (pin "1") (pinfunction "1_1") (pintype "input"))
    )
    (net (code "73") (name "TRG2") (class "Default")
      (node (ref "P3F") (pin "4") (pinfunction "4_4") (pintype "unspecified"))
      (node (ref "Q2") (pin "2") (pinfunction "E_2") (pintype "unspecified"))
      (node (ref "R12") (pin "1") (pinfunction "1_1") (pintype "input"))
    )
    (net (code "74") (name "TRG3") (class "Default")
      (node (ref "P4F") (pin "1") (pinfunction "1_1") (pintype "input"))
      (node (ref "Q3") (pin "2") (pinfunction "E_2") (pintype "unspecified"))
      (node (ref "R14") (pin "1") (pinfunction "1_1") (pintype "input"))
    )
    (net (code "75") (name "TRG4") (class "Default")
      (node (ref "P4F") (pin "5") (pinfunction "5_5") (pintype "input"))
      (node (ref "Q4") (pin "2") (pinfunction "E_2") (pintype "unspecified"))
      (node (ref "R16") (pin "1") (pinfunction "1_1") (pintype "input"))
    )
    (net (code "76") (name "TRG5") (class "Default")
      (node (ref "P4F") (pin "2") (pinfunction "2_2") (pintype "input"))
      (node (ref "Q5") (pin "2") (pinfunction "E_2") (pintype "unspecified"))
      (node (ref "R19") (pin "1") (pinfunction "1_1") (pintype "input"))
    )
    (net (code "77") (name "TRG6") (class "Default")
      (node (ref "P4F") (pin "6") (pinfunction "6_6") (pintype "input"))
      (node (ref "Q6") (pin "2") (pinfunction "E_2") (pintype "unspecified"))
      (node (ref "R21") (pin "1") (pinfunction "1_1") (pintype "input"))
    )
    (net (code "78") (name "TRG7") (class "Default")
      (node (ref "P5F") (pin "1") (pinfunction "1_1") (pintype "unspecified"))
      (node (ref "Q7") (pin "2") (pinfunction "E_2") (pintype "unspecified"))
      (node (ref "R22") (pin "1") (pinfunction "1_1") (pintype "input"))
    )
    (net (code "79") (name "TRG8") (class "Default")
      (node (ref "P5F") (pin "3") (pinfunction "3_3") (pintype "unspecified"))
      (node (ref "Q8") (pin "2") (pinfunction "E_2") (pintype "unspecified"))
      (node (ref "R24") (pin "1") (pinfunction "1_1") (pintype "input"))
    )
    (net (code "80") (name "TRG9") (class "Default")
      (node (ref "P5F") (pin "2") (pinfunction "2_2") (pintype "unspecified"))
      (node (ref "Q9") (pin "2") (pinfunction "E_2") (pintype "unspecified"))
      (node (ref "R26") (pin "1") (pinfunction "1_1") (pintype "input"))
    )
    (net (code "81") (name "TRG10") (class "Default")
      (node (ref "P5F") (pin "4") (pinfunction "4_4") (pintype "unspecified"))
      (node (ref "Q10") (pin "2") (pinfunction "E_2") (pintype "unspecified"))
      (node (ref "R28") (pin "1") (pinfunction "1_1") (pintype "input"))
    )
    (net (code "82") (name "unconnected-(CC1-3-PadP$2)") (class "Default")
      (node (ref "CC1") (pin "P$2") (pinfunction "3_P$2") (pintype "bidirectional+no_connect"))
    )
    (net (code "83") (name "unconnected-(CC2-3-PadP$2)") (class "Default")
      (node (ref "CC2") (pin "P$2") (pinfunction "3_P$2") (pintype "bidirectional+no_connect"))
    )
    (net (code "84") (name "unconnected-(CC3-3-PadP$2)") (class "Default")
      (node (ref "CC3") (pin "P$2") (pinfunction "3_P$2") (pintype "bidirectional+no_connect"))
    )
    (net (code "85") (name "unconnected-(CC4-3-PadP$2)") (class "Default")
      (node (ref "CC4") (pin "P$2") (pinfunction "3_P$2") (pintype "bidirectional+no_connect"))
    )
    (net (code "86") (name "unconnected-(CC5-3-PadP$2)") (class "Default")
      (node (ref "CC5") (pin "P$2") (pinfunction "3_P$2") (pintype "bidirectional+no_connect"))
    )
    (net (code "87") (name "unconnected-(CC6-3-PadP$2)") (class "Default")
      (node (ref "CC6") (pin "P$2") (pinfunction "3_P$2") (pintype "bidirectional+no_connect"))
    )
    (net (code "88") (name "unconnected-(MIDI-Pad1)") (class "Default")
      (node (ref "MIDI") (pin "1") (pinfunction "1_1") (pintype "unspecified+no_connect"))
    )
    (net (code "89") (name "unconnected-(MIDI-Pad3)") (class "Default")
      (node (ref "MIDI") (pin "3") (pinfunction "3_3") (pintype "unspecified+no_connect"))
    )
    (net (code "90") (name "unconnected-(P4-Pad1)") (class "Default")
      (node (ref "P4") (pin "1") (pinfunction "1_1") (pintype "unspecified+no_connect"))
    )
    (net (code "91") (name "unconnected-(P4-Pad2)") (class "Default")
      (node (ref "P4") (pin "2") (pinfunction "2_2") (pintype "unspecified+no_connect"))
    )
    (net (code "92") (name "unconnected-(TRG1-3-PadP$2)") (class "Default")
      (node (ref "TRG1") (pin "P$2") (pinfunction "3_P$2") (pintype "bidirectional+no_connect"))
    )
    (net (code "93") (name "unconnected-(TRG2-3-PadP$2)") (class "Default")
      (node (ref "TRG2") (pin "P$2") (pinfunction "3_P$2") (pintype "bidirectional+no_connect"))
    )
    (net (code "94") (name "unconnected-(TRG3-3-PadP$2)") (class "Default")
      (node (ref "TRG3") (pin "P$2") (pinfunction "3_P$2") (pintype "bidirectional+no_connect"))
    )
    (net (code "95") (name "unconnected-(TRG4-3-PadP$2)") (class "Default")
      (node (ref "TRG4") (pin "P$2") (pinfunction "3_P$2") (pintype "bidirectional+no_connect"))
    )
    (net (code "96") (name "unconnected-(TRG5-3-PadP$2)") (class "Default")
      (node (ref "TRG5") (pin "P$2") (pinfunction "3_P$2") (pintype "bidirectional+no_connect"))
    )
    (net (code "97") (name "unconnected-(TRG6-3-PadP$2)") (class "Default")
      (node (ref "TRG6") (pin "P$2") (pinfunction "3_P$2") (pintype "bidirectional+no_connect"))
    )
    (net (code "98") (name "unconnected-(TRG7-3-PadP$2)") (class "Default")
      (node (ref "TRG7") (pin "P$2") (pinfunction "3_P$2") (pintype "bidirectional+no_connect"))
    )
    (net (code "99") (name "unconnected-(TRG8-3-PadP$2)") (class "Default")
      (node (ref "TRG8") (pin "P$2") (pinfunction "3_P$2") (pintype "bidirectional+no_connect"))
    )
    (net (code "100") (name "unconnected-(TRG9-3-PadP$2)") (class "Default")
      (node (ref "TRG9") (pin "P$2") (pinfunction "3_P$2") (pintype "bidirectional+no_connect"))
    )
    (net (code "101") (name "unconnected-(TRG10-3-PadP$2)") (class "Default")
      (node (ref "TRG10") (pin "P$2") (pinfunction "3_P$2") (pintype "bidirectional+no_connect"))
    )
    (net (code "102") (name "unconnected-(U1-3V3-Pad17)") (class "Default")
      (node (ref "U1") (pin "17") (pinfunction "3V3_17") (pintype "unspecified+no_connect"))
    )
    (net (code "103") (name "unconnected-(U1-GND-Pad4)") (class "Default")
      (node (ref "U1") (pin "4") (pinfunction "GND_4") (pintype "unspecified+no_connect"))
    )
    (net (code "104") (name "unconnected-(U1-REF-Pad18)") (class "Default")
      (node (ref "U1") (pin "18") (pinfunction "REF_18") (pintype "unspecified+no_connect"))
    )
    (net (code "105") (name "unconnected-(U1-RST-Pad3)") (class "Default")
      (node (ref "U1") (pin "3") (pinfunction "RST_3") (pintype "unspecified+no_connect"))
    )
    (net (code "106") (name "unconnected-(U1-RST-Pad28)") (class "Default")
      (node (ref "U1") (pin "28") (pinfunction "RST_28") (pintype "unspecified+no_connect"))
    )
    (net (code "107") (name "unconnected-(U1-RXD-Pad2)") (class "Default")
      (node (ref "U1") (pin "2") (pinfunction "RXD_2") (pintype "unspecified+no_connect"))
    )
    (net (code "108") (name "unconnected-(U1-Vin-Pad30)") (class "Default")
      (node (ref "U1") (pin "30") (pinfunction "Vin_30") (pintype "unspecified+no_connect"))
    )
  )
)
